# Power.net
KiCad netlist of a schematic drawn in Altium Designer
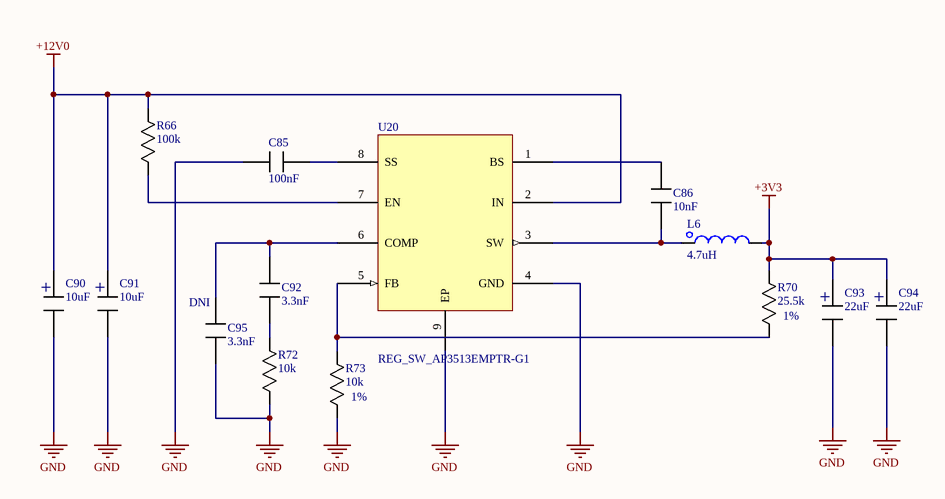
[diagram p0: Power.SchDoc]

(export (version "E")
  (design (tool "Eeschema 10.0.6"))
  (components
    (comp (ref "C85")
      (value "100nF")
      (footprint "0603")
      (description "Capacitor")
      (fields (field (name "MFG") "Samsung"))
      (libsource (lib "ADAPTONE_CARTE_DE_SON") (part "Capacitor"))
    )
    (comp (ref "C86")
      (value "10nF")
      (footprint "0603")
      (description "Capacitor")
      (fields (field (name "MFG") "Samsung"))
      (libsource (lib "ADAPTONE_CARTE_DE_SON") (part "Capacitor"))
    )
    (comp (ref "C90")
      (value "10uF")
      (footprint "CAP_RAD_SMD_DIA157")
      (description "Capacitor")
      (fields (field (name "MFG") "Nichicon") (field (name "Comment") "Capacitor_Polarized"))
      (libsource (lib "ADAPTONE_CARTE_DE_SON") (part "Capacitor_Polarized"))
    )
    (comp (ref "C91")
      (value "10uF")
      (footprint "CAP_RAD_SMD_DIA157")
      (description "Capacitor")
      (fields (field (name "MFG") "Nichicon") (field (name "Comment") "Capacitor_Polarized"))
      (libsource (lib "ADAPTONE_CARTE_DE_SON") (part "Capacitor_Polarized"))
    )
    (comp (ref "C92")
      (value "3.3nF")
      (footprint "0603")
      (description "Capacitor")
      (fields (field (name "MFG") "Samsung"))
      (libsource (lib "ADAPTONE_CARTE_DE_SON") (part "Capacitor"))
    )
    (comp (ref "C93")
      (value "22uF")
      (footprint "CAP_RAD_SMD_DIA157")
      (description "Capacitor")
      (fields (field (name "MFG") "Nichicon") (field (name "Comment") "Capacitor_Polarized"))
      (libsource (lib "ADAPTONE_CARTE_DE_SON") (part "Capacitor_Polarized"))
    )
    (comp (ref "C94")
      (value "22uF")
      (footprint "CAP_RAD_SMD_DIA157")
      (description "Capacitor")
      (fields (field (name "MFG") "Nichicon") (field (name "Comment") "Capacitor_Polarized"))
      (libsource (lib "ADAPTONE_CARTE_DE_SON") (part "Capacitor_Polarized"))
    )
    (comp (ref "C95")
      (value "3.3nF")
      (footprint "0603")
      (description "Capacitor")
      (fields (field (name "MFG") "Samsung") (field (name "NOTE") "DNI"))
      (libsource (lib "ADAPTONE_CARTE_DE_SON") (part "Capacitor"))
    )
    (comp (ref "L6")
      (value "4.7uH")
      (footprint "SRN5040-4R7M")
      (description "Inductor")
      (fields (field (name "MFG") "Bourns Inc."))
      (libsource (lib "ADAPTONE_CARTE_DE_SON") (part "Inductor"))
    )
    (comp (ref "R66")
      (value "100k")
      (footprint "0603")
      (description "Resistor")
      (fields (field (name "MFG") "Stackpole Electronics Inc"))
      (libsource (lib "ADAPTONE_CARTE_DE_SON") (part "Resistor"))
    )
    (comp (ref "R70")
      (value "25.5k")
      (footprint "0603")
      (description "Resistor")
      (fields (field (name "MFG") "Stackpole Electronics Inc") (field (name "TOLERANCE") "1%"))
      (libsource (lib "ADAPTONE_CARTE_DE_SON") (part "Resistor"))
    )
    (comp (ref "R72")
      (value "10k")
      (footprint "0603")
      (description "Resistor")
      (fields (field (name "MFG") "Yageo"))
      (libsource (lib "ADAPTONE_CARTE_DE_SON") (part "Resistor"))
    )
    (comp (ref "R73")
      (value "10k")
      (footprint "0603")
      (description "Resistor")
      (fields (field (name "MFG") "Stackpole Electronics Inc") (field (name "TOLERANCE") "1%"))
      (libsource (lib "ADAPTONE_CARTE_DE_SON") (part "Resistor"))
    )
    (comp (ref "U20")
      (value "REG_SW_AP3513EMPTR-G1")
      (footprint "AP3513EMPTR-G1")
      (fields
        (field (name "MFG") "Diodes Incorporated")
        (field (name "MFG PART NUMBER") "AP3513EMPTR-G1")
        (field (name "CREATEDBY") "Emile Laplante")
        (field (name "VERIFIEDBY") "*")
      )
      (libsource (lib "LIB_ADAPTONE_EMILE_LAPLANTE") (part "REG_SW_AP3513EMPTR-G1"))
    )
  )
  (nets
    (net (code "1") (name "+3V3") (class "Default")
      (node (ref "C93") (pin "+") (pintype "passive"))
      (node (ref "C94") (pin "+") (pintype "passive"))
      (node (ref "L6") (pin "2") (pintype "passive"))
      (node (ref "R70") (pin "1") (pintype "passive"))
    )
    (net (code "2") (name "+12V0") (class "Default")
      (node (ref "C90") (pin "+") (pintype "passive"))
      (node (ref "C91") (pin "+") (pintype "passive"))
      (node (ref "R66") (pin "2") (pintype "passive"))
      (node (ref "U20") (pin "2") (pinfunction "IN_2") (pintype "power_in"))
    )
    (net (code "3") (name "GND") (class "Default")
      (node (ref "C85") (pin "1") (pintype "passive"))
      (node (ref "C90") (pin "-") (pintype "passive"))
      (node (ref "C91") (pin "-") (pintype "passive"))
      (node (ref "C93") (pin "-") (pintype "passive"))
      (node (ref "C94") (pin "-") (pintype "passive"))
      (node (ref "C95") (pin "2") (pintype "passive"))
      (node (ref "R72") (pin "2") (pintype "passive"))
      (node (ref "R73") (pin "2") (pintype "passive"))
      (node (ref "U20") (pin "4") (pinfunction "GND_4") (pintype "passive"))
      (node (ref "U20") (pin "9") (pinfunction "EP_9") (pintype "passive"))
    )
    (net (code "4") (name "Net-(C92-Pad2)") (class "Default")
      (node (ref "C92") (pin "2") (pintype "passive"))
      (node (ref "R72") (pin "1") (pintype "passive"))
    )
    (net (code "5") (name "Net-(U20-BS)") (class "Default")
      (node (ref "C86") (pin "1") (pintype "passive"))
      (node (ref "U20") (pin "1") (pinfunction "BS_1") (pintype "passive"))
    )
    (net (code "6") (name "Net-(U20-COMP)") (class "Default")
      (node (ref "C92") (pin "1") (pintype "passive"))
      (node (ref "C95") (pin "1") (pintype "passive"))
      (node (ref "U20") (pin "6") (pinfunction "COMP_6") (pintype "passive"))
    )
    (net (code "7") (name "Net-(U20-EN)") (class "Default")
      (node (ref "R66") (pin "1") (pintype "passive"))
      (node (ref "U20") (pin "7") (pinfunction "EN_7") (pintype "passive"))
    )
    (net (code "8") (name "Net-(U20-FB)") (class "Default")
      (node (ref "R70") (pin "2") (pintype "passive"))
      (node (ref "R73") (pin "1") (pintype "passive"))
      (node (ref "U20") (pin "5") (pinfunction "FB_5") (pintype "input"))
    )
    (net (code "9") (name "Net-(U20-SS)") (class "Default")
      (node (ref "C85") (pin "2") (pintype "passive"))
      (node (ref "U20") (pin "8") (pinfunction "SS_8") (pintype "passive"))
    )
    (net (code "10") (name "Net-(U20-SW)") (class "Default")
      (node (ref "C86") (pin "2") (pintype "passive"))
      (node (ref "L6") (pin "1") (pintype "passive"))
      (node (ref "U20") (pin "3") (pinfunction "SW_3") (pintype "output"))
    )
  )
)
